# 15_RK3588_VCCIO5.net
KiCad netlist of a schematic drawn in Altium Designer
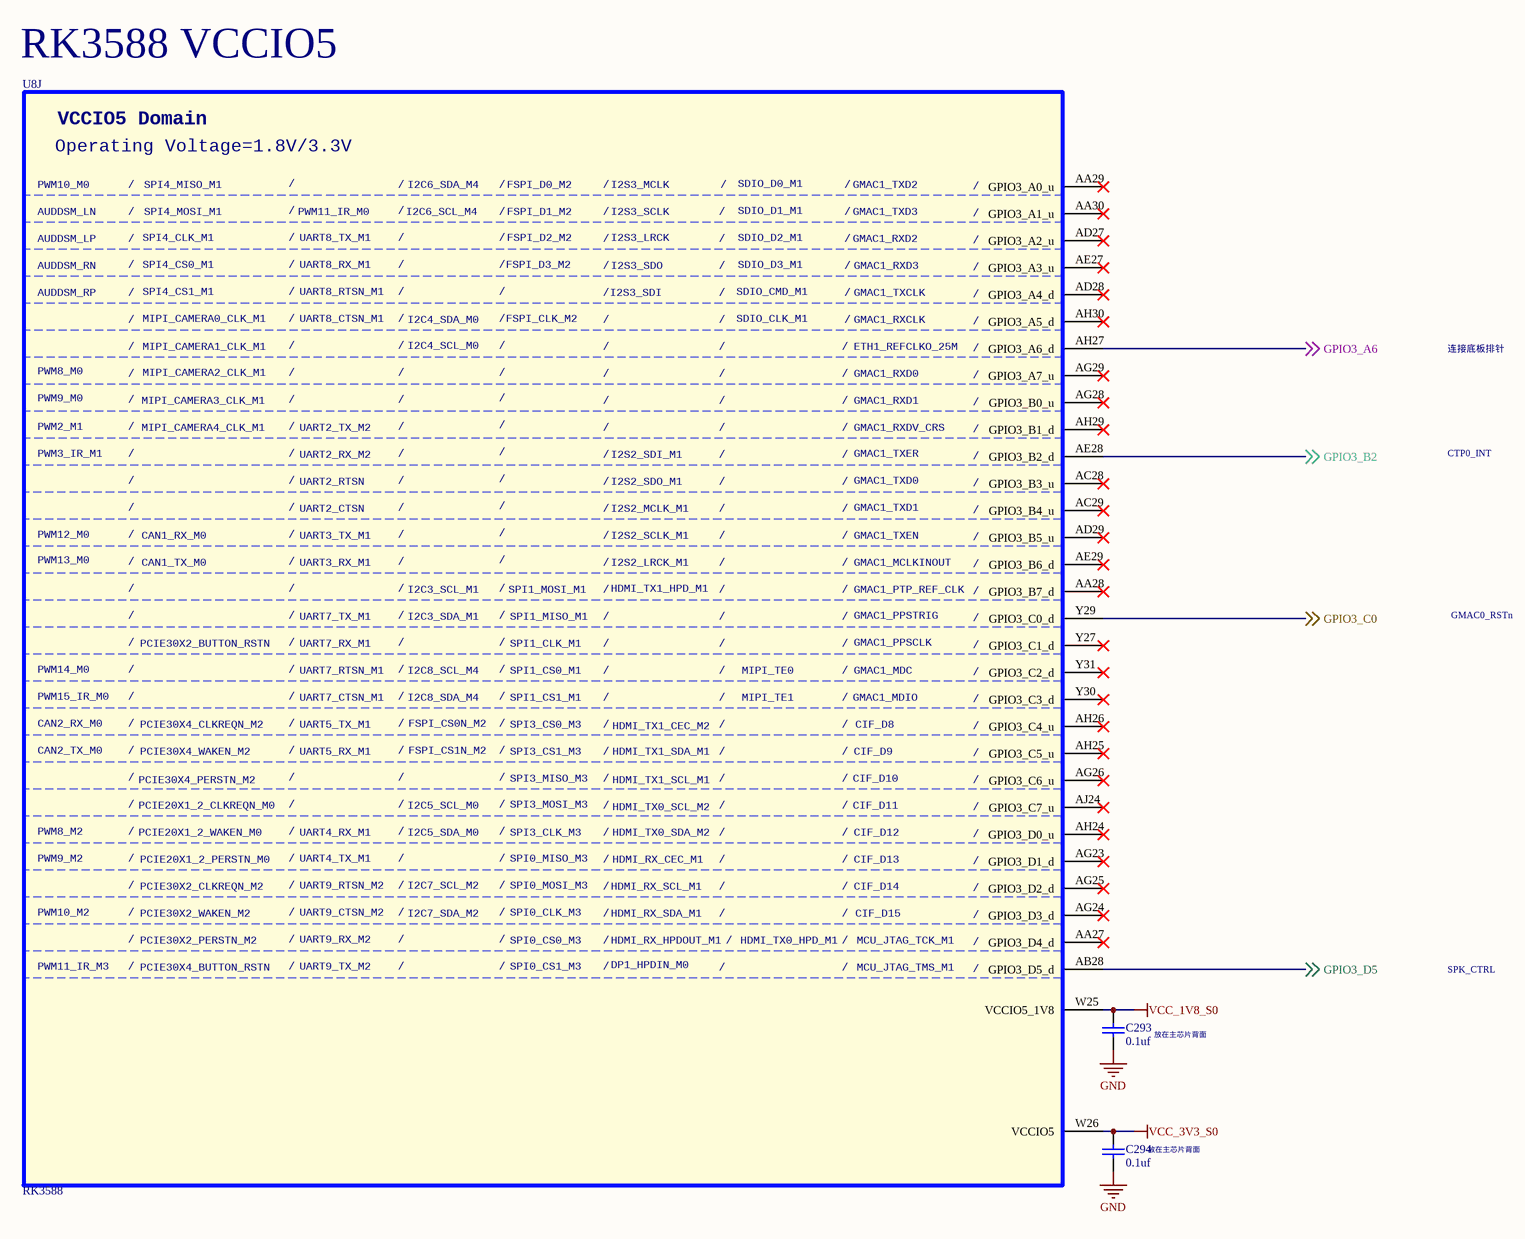
[diagram p0: 15.RK3588_VCCIO5.SchDoc]

(export (version "E")
  (design (tool "Eeschema 10.0.6"))
  (components
    (comp (ref "C293")
      (value "0.1uf")
      (footprint "0.PCB1:C0201_L")
      (description "贴片电容/MLCC电容")
      (libsource (lib "RK3588") (part "C"))
    )
    (comp (ref "C294")
      (value "0.1uf")
      (footprint "0.PCB1:C0201_L")
      (description "贴片电容/MLCC电容")
      (libsource (lib "RK3588") (part "C"))
    )
    (comp (ref "U8")
      (value "RK3588")
      (footprint "0.PCB1:BGA1088_23R00X23R00X2R00")
      (description "ROCKCHIP SOC")
      (libsource (lib "RK3588") (part "SOC_RK3588"))
    )
  )
  (nets
    (net (code "1") (name "GND") (class "Default")
      (node (ref "C293") (pin "1") (pinfunction "1_1") (pintype "passive"))
      (node (ref "C294") (pin "1") (pinfunction "1_1") (pintype "passive"))
    )
    (net (code "2") (name "GPIO3_A6") (class "Default")
      (node (ref "U8") (pin "AH27") (pinfunction "GPIO3_A6_d_AH27") (pintype "passive"))
    )
    (net (code "3") (name "GPIO3_B2") (class "Default")
      (node (ref "U8") (pin "AE28") (pinfunction "GPIO3_B2_d_AE28") (pintype "passive"))
    )
    (net (code "4") (name "GPIO3_C0") (class "Default")
      (node (ref "U8") (pin "Y29") (pinfunction "GPIO3_C0_d_Y29") (pintype "passive"))
    )
    (net (code "5") (name "GPIO3_D5") (class "Default")
      (node (ref "U8") (pin "AB28") (pinfunction "GPIO3_D5_d_AB28") (pintype "passive"))
    )
    (net (code "6") (name "VCC_1V8_S0") (class "Default")
      (node (ref "C293") (pin "2") (pinfunction "2_2") (pintype "passive"))
      (node (ref "U8") (pin "W25") (pinfunction "VCCIO5_1V8_W25") (pintype "passive"))
    )
    (net (code "7") (name "VCC_3V3_S0") (class "Default")
      (node (ref "C294") (pin "2") (pinfunction "2_2") (pintype "passive"))
      (node (ref "U8") (pin "W26") (pinfunction "VCCIO5_W26") (pintype "passive"))
    )
    (net (code "8") (name "unconnected-(U8J-GPIO3_A0_u-PadAA29)") (class "Default")
      (node (ref "U8") (pin "AA29") (pinfunction "GPIO3_A0_u_AA29") (pintype "passive+no_connect"))
    )
    (net (code "9") (name "unconnected-(U8J-GPIO3_A1_u-PadAA30)") (class "Default")
      (node (ref "U8") (pin "AA30") (pinfunction "GPIO3_A1_u_AA30") (pintype "passive+no_connect"))
    )
    (net (code "10") (name "unconnected-(U8J-GPIO3_A2_u-PadAD27)") (class "Default")
      (node (ref "U8") (pin "AD27") (pinfunction "GPIO3_A2_u_AD27") (pintype "passive+no_connect"))
    )
    (net (code "11") (name "unconnected-(U8J-GPIO3_A3_u-PadAE27)") (class "Default")
      (node (ref "U8") (pin "AE27") (pinfunction "GPIO3_A3_u_AE27") (pintype "passive+no_connect"))
    )
    (net (code "12") (name "unconnected-(U8J-GPIO3_A4_d-PadAD28)") (class "Default")
      (node (ref "U8") (pin "AD28") (pinfunction "GPIO3_A4_d_AD28") (pintype "passive+no_connect"))
    )
    (net (code "13") (name "unconnected-(U8J-GPIO3_A5_d-PadAH30)") (class "Default")
      (node (ref "U8") (pin "AH30") (pinfunction "GPIO3_A5_d_AH30") (pintype "passive+no_connect"))
    )
    (net (code "14") (name "unconnected-(U8J-GPIO3_A7_u-PadAG29)") (class "Default")
      (node (ref "U8") (pin "AG29") (pinfunction "GPIO3_A7_u_AG29") (pintype "passive+no_connect"))
    )
    (net (code "15") (name "unconnected-(U8J-GPIO3_B0_u-PadAG28)") (class "Default")
      (node (ref "U8") (pin "AG28") (pinfunction "GPIO3_B0_u_AG28") (pintype "passive+no_connect"))
    )
    (net (code "16") (name "unconnected-(U8J-GPIO3_B1_d-PadAH29)") (class "Default")
      (node (ref "U8") (pin "AH29") (pinfunction "GPIO3_B1_d_AH29") (pintype "passive+no_connect"))
    )
    (net (code "17") (name "unconnected-(U8J-GPIO3_B3_u-PadAC28)") (class "Default")
      (node (ref "U8") (pin "AC28") (pinfunction "GPIO3_B3_u_AC28") (pintype "passive+no_connect"))
    )
    (net (code "18") (name "unconnected-(U8J-GPIO3_B4_u-PadAC29)") (class "Default")
      (node (ref "U8") (pin "AC29") (pinfunction "GPIO3_B4_u_AC29") (pintype "passive+no_connect"))
    )
    (net (code "19") (name "unconnected-(U8J-GPIO3_B5_u-PadAD29)") (class "Default")
      (node (ref "U8") (pin "AD29") (pinfunction "GPIO3_B5_u_AD29") (pintype "passive+no_connect"))
    )
    (net (code "20") (name "unconnected-(U8J-GPIO3_B6_d-PadAE29)") (class "Default")
      (node (ref "U8") (pin "AE29") (pinfunction "GPIO3_B6_d_AE29") (pintype "passive+no_connect"))
    )
    (net (code "21") (name "unconnected-(U8J-GPIO3_B7_d-PadAA28)") (class "Default")
      (node (ref "U8") (pin "AA28") (pinfunction "GPIO3_B7_d_AA28") (pintype "passive+no_connect"))
    )
    (net (code "22") (name "unconnected-(U8J-GPIO3_C1_d-PadY27)") (class "Default")
      (node (ref "U8") (pin "Y27") (pinfunction "GPIO3_C1_d_Y27") (pintype "passive+no_connect"))
    )
    (net (code "23") (name "unconnected-(U8J-GPIO3_C2_d-PadY31)") (class "Default")
      (node (ref "U8") (pin "Y31") (pinfunction "GPIO3_C2_d_Y31") (pintype "passive+no_connect"))
    )
    (net (code "24") (name "unconnected-(U8J-GPIO3_C3_d-PadY30)") (class "Default")
      (node (ref "U8") (pin "Y30") (pinfunction "GPIO3_C3_d_Y30") (pintype "passive+no_connect"))
    )
    (net (code "25") (name "unconnected-(U8J-GPIO3_C4_u-PadAH26)") (class "Default")
      (node (ref "U8") (pin "AH26") (pinfunction "GPIO3_C4_u_AH26") (pintype "passive+no_connect"))
    )
    (net (code "26") (name "unconnected-(U8J-GPIO3_C5_u-PadAH25)") (class "Default")
      (node (ref "U8") (pin "AH25") (pinfunction "GPIO3_C5_u_AH25") (pintype "passive+no_connect"))
    )
    (net (code "27") (name "unconnected-(U8J-GPIO3_C6_u-PadAG26)") (class "Default")
      (node (ref "U8") (pin "AG26") (pinfunction "GPIO3_C6_u_AG26") (pintype "passive+no_connect"))
    )
    (net (code "28") (name "unconnected-(U8J-GPIO3_C7_u-PadAJ24)") (class "Default")
      (node (ref "U8") (pin "AJ24") (pinfunction "GPIO3_C7_u_AJ24") (pintype "passive+no_connect"))
    )
    (net (code "29") (name "unconnected-(U8J-GPIO3_D0_u-PadAH24)") (class "Default")
      (node (ref "U8") (pin "AH24") (pinfunction "GPIO3_D0_u_AH24") (pintype "passive+no_connect"))
    )
    (net (code "30") (name "unconnected-(U8J-GPIO3_D1_d-PadAG23)") (class "Default")
      (node (ref "U8") (pin "AG23") (pinfunction "GPIO3_D1_d_AG23") (pintype "passive+no_connect"))
    )
    (net (code "31") (name "unconnected-(U8J-GPIO3_D2_d-PadAG25)") (class "Default")
      (node (ref "U8") (pin "AG25") (pinfunction "GPIO3_D2_d_AG25") (pintype "passive+no_connect"))
    )
    (net (code "32") (name "unconnected-(U8J-GPIO3_D3_d-PadAG24)") (class "Default")
      (node (ref "U8") (pin "AG24") (pinfunction "GPIO3_D3_d_AG24") (pintype "passive+no_connect"))
    )
    (net (code "33") (name "unconnected-(U8J-GPIO3_D4_d-PadAA27)") (class "Default")
      (node (ref "U8") (pin "AA27") (pinfunction "GPIO3_D4_d_AA27") (pintype "passive+no_connect"))
    )
  )
)
